# master_devon_routed.net
KiCad netlist of a schematic drawn in EAGLE
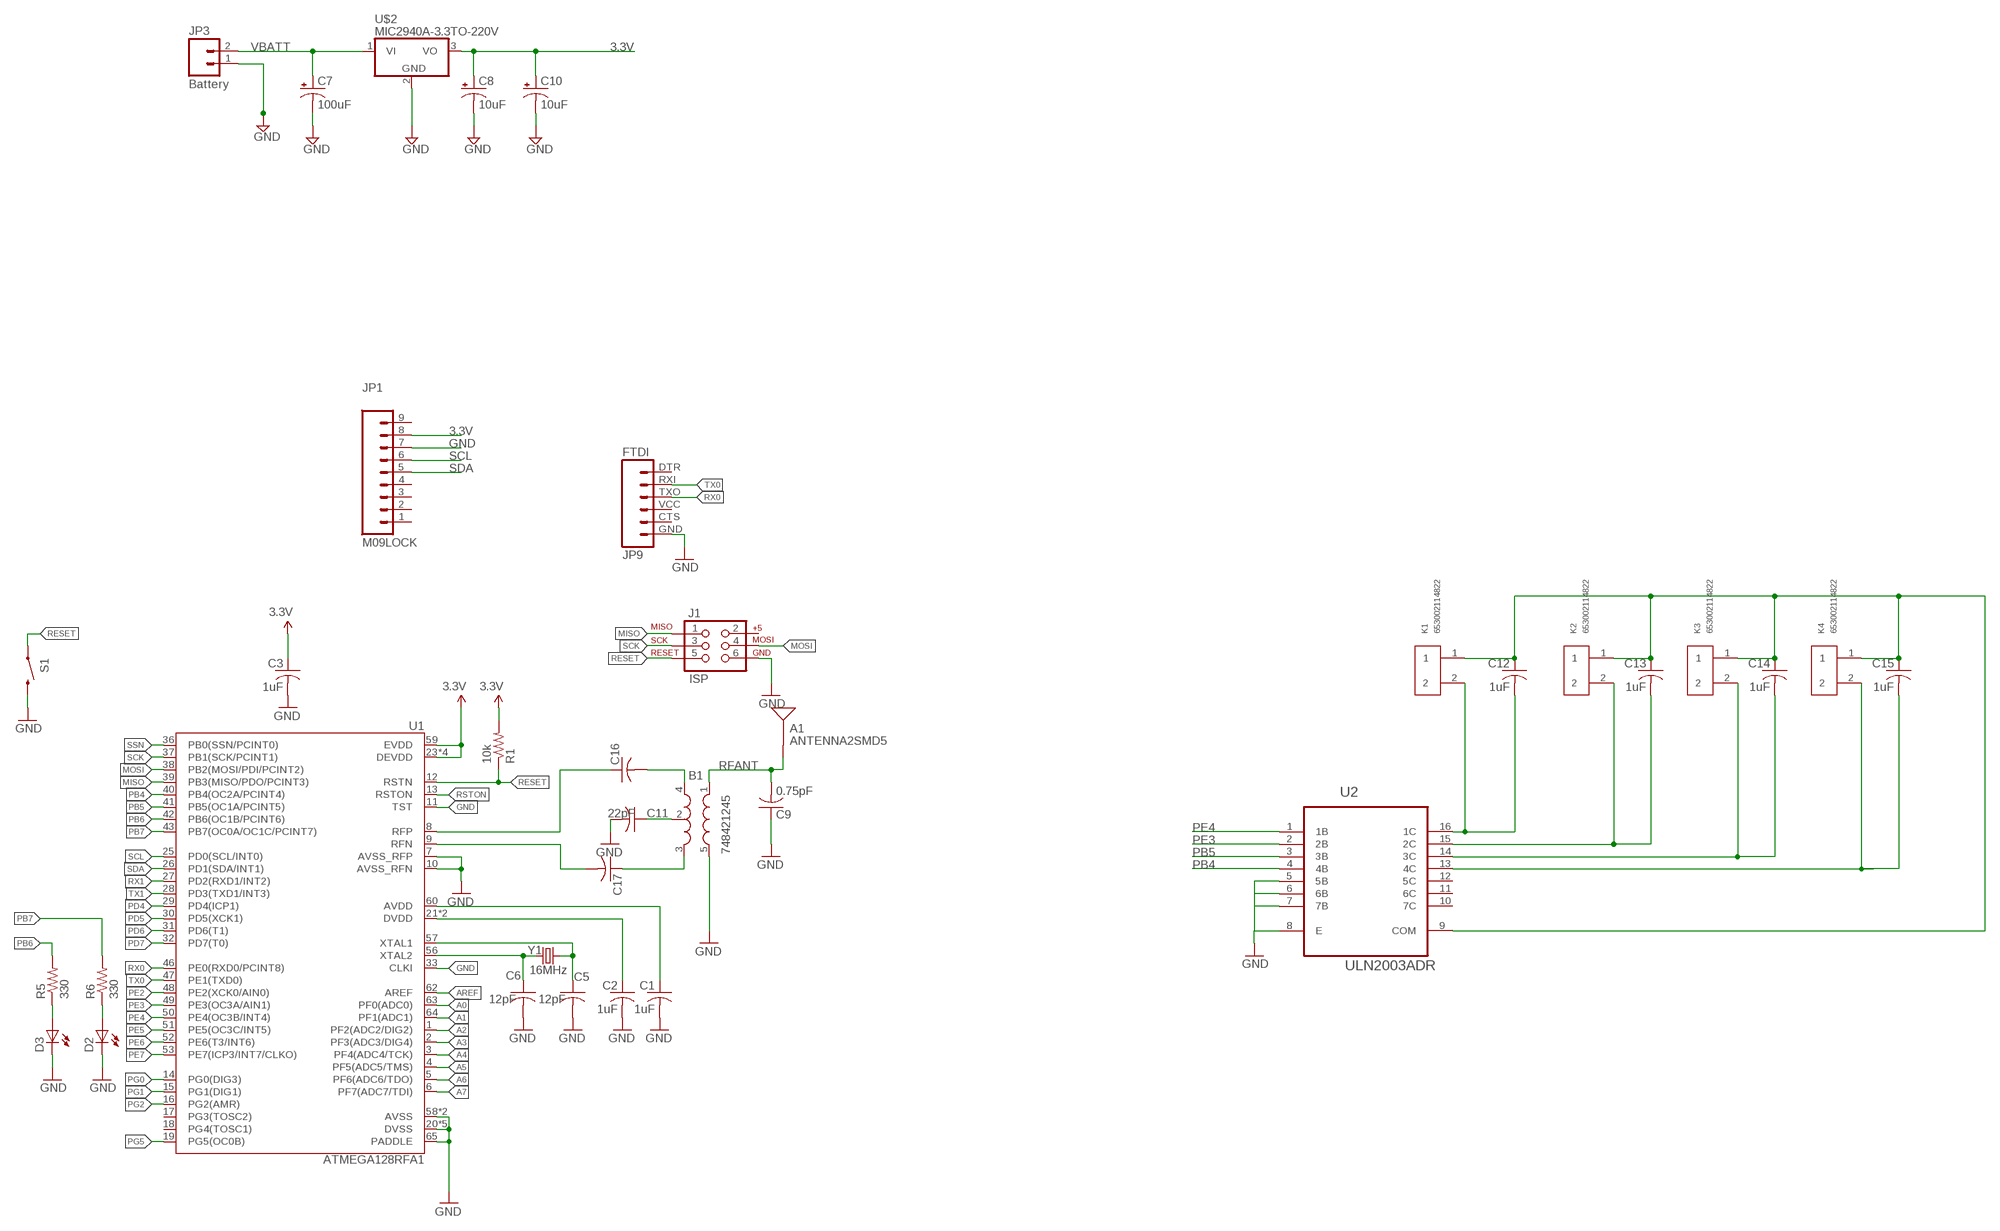
[diagram p0: schematic, sheet 1]

(export (version "E")
  (design (tool "Eeschema 10.0.6"))
  (components
    (comp (ref "A1")
      (value "ANTENNA2SMD5")
      (footprint "eagle-import:ANTENNA-CHIP5")
      (libsource (lib "eagle-import") (part "ANTENNA2SMD5"))
    )
    (comp (ref "B1")
      (value "748421245")
      (footprint "eagle-import:BALUN")
      (libsource (lib "eagle-import") (part "BALUN0805"))
    )
    (comp (ref "C1")
      (value "1uF")
      (footprint "eagle-import:C0805")
      (libsource (lib "eagle-import") (part "C-USC0805"))
    )
    (comp (ref "C2")
      (value "1uF")
      (footprint "eagle-import:C0805")
      (libsource (lib "eagle-import") (part "C-USC0805"))
    )
    (comp (ref "C3")
      (value "1uF")
      (footprint "eagle-import:C0805")
      (libsource (lib "eagle-import") (part "C-USC0805"))
    )
    (comp (ref "C5")
      (value "12pF")
      (footprint "eagle-import:C0805")
      (libsource (lib "eagle-import") (part "C-USC0805"))
    )
    (comp (ref "C6")
      (value "12pF")
      (footprint "eagle-import:C0805")
      (libsource (lib "eagle-import") (part "C-USC0805"))
    )
    (comp (ref "C7")
      (value "100uF")
      (footprint "eagle-import:E3,5-8")
      (libsource (lib "eagle-import") (part "CPOL-USE3.5-8"))
    )
    (comp (ref "C8")
      (value "10uF")
      (footprint "eagle-import:E2,5-5")
      (libsource (lib "eagle-import") (part "CPOL-USE2.5-5"))
    )
    (comp (ref "C9")
      (value "0.75pF")
      (footprint "eagle-import:C0805")
      (libsource (lib "eagle-import") (part "C-USC0805"))
    )
    (comp (ref "C10")
      (value "10uF")
      (footprint "eagle-import:E2,5-5")
      (libsource (lib "eagle-import") (part "CPOL-USE2.5-5"))
    )
    (comp (ref "C11")
      (value "22pF")
      (footprint "eagle-import:C0805")
      (libsource (lib "eagle-import") (part "C-USC0805"))
    )
    (comp (ref "C12")
      (value "1uF")
      (footprint "eagle-import:C0805")
      (libsource (lib "eagle-import") (part "C-USC0805"))
    )
    (comp (ref "C13")
      (value "1uF")
      (footprint "eagle-import:C0805")
      (libsource (lib "eagle-import") (part "C-USC0805"))
    )
    (comp (ref "C14")
      (value "1uF")
      (footprint "eagle-import:C0805")
      (libsource (lib "eagle-import") (part "C-USC0805"))
    )
    (comp (ref "C15")
      (value "1uF")
      (footprint "eagle-import:C0805")
      (libsource (lib "eagle-import") (part "C-USC0805"))
    )
    (comp (ref "C16")
      (value "C-USC0805")
      (footprint "eagle-import:C0805")
      (libsource (lib "eagle-import") (part "C-USC0805"))
    )
    (comp (ref "C17")
      (value "C-USC0805")
      (footprint "eagle-import:C0805")
      (libsource (lib "eagle-import") (part "C-USC0805"))
    )
    (comp (ref "D2")
      (value "LEDCHIP-LED0805")
      (footprint "eagle-import:CHIP-LED0805")
      (libsource (lib "eagle-import") (part "LEDCHIP-LED0805"))
    )
    (comp (ref "D3")
      (value "LEDCHIP-LED0805")
      (footprint "eagle-import:CHIP-LED0805")
      (libsource (lib "eagle-import") (part "LEDCHIP-LED0805"))
    )
    (comp (ref "J1")
      (value "ISP")
      (footprint "eagle-import:2X3-NS")
      (libsource (lib "eagle-import") (part "AVR_SPI_PRG_6NS"))
    )
    (comp (ref "JP1")
      (value "M09LOCK")
      (footprint "eagle-import:1X09_LOCK")
      (libsource (lib "eagle-import") (part "M09LOCK"))
    )
    (comp (ref "JP3")
      (value "Battery")
      (footprint "eagle-import:1X02")
      (libsource (lib "eagle-import") (part "M02PTH"))
    )
    (comp (ref "JP9")
      (value "FTDI")
      (footprint "eagle-import:FTDI_BASIC")
      (libsource (lib "eagle-import") (part "FTDI_BASICPTH"))
    )
    (comp (ref "K1")
      (value "653002114822")
      (footprint "eagle-import:653002114822")
      (libsource (lib "eagle-import") (part "653002114822"))
    )
    (comp (ref "K2")
      (value "653002114822")
      (footprint "eagle-import:653002114822")
      (libsource (lib "eagle-import") (part "653002114822"))
    )
    (comp (ref "K3")
      (value "653002114822")
      (footprint "eagle-import:653002114822")
      (libsource (lib "eagle-import") (part "653002114822"))
    )
    (comp (ref "K4")
      (value "653002114822")
      (footprint "eagle-import:653002114822")
      (libsource (lib "eagle-import") (part "653002114822"))
    )
    (comp (ref "R1")
      (value "10k")
      (footprint "eagle-import:R0805")
      (libsource (lib "eagle-import") (part "R-US_R0805"))
    )
    (comp (ref "R5")
      (value "330")
      (footprint "eagle-import:R0805")
      (libsource (lib "eagle-import") (part "R-US_R0805"))
    )
    (comp (ref "R6")
      (value "330")
      (footprint "eagle-import:R0805")
      (libsource (lib "eagle-import") (part "R-US_R0805"))
    )
    (comp (ref "S1")
      (value "SWITCH-MOMENTARY-2SMD")
      (footprint "eagle-import:TACTILE_SWITCH_SMD")
      (libsource (lib "eagle-import") (part "SWITCH-MOMENTARY-2SMD"))
    )
    (comp (ref "U$2")
      (value "MIC2940A-3.3TO-220V")
      (footprint "eagle-import:TO-220V")
      (libsource (lib "eagle-import") (part "MIC2940A-3.3TO-220V"))
    )
    (comp (ref "U1")
      (value "ATMEGA128RFA1")
      (footprint "eagle-import:QFN-64")
      (libsource (lib "eagle-import") (part "ATMEGA128RFA1"))
    )
    (comp (ref "U2")
      (value "ULN2003ADR")
      (footprint "eagle-import:SOIC127P600X175-16N")
      (libsource (lib "eagle-import") (part "ULN2003ADR"))
    )
    (comp (ref "Y1")
      (value "16MHz")
      (footprint "eagle-import:CRYSTAL-SMD-5X3")
      (libsource (lib "eagle-import") (part "CRYSTAL5X3"))
    )
  )
  (nets
    (net (code "1") (name "/RFANT") (class "Default")
      (node (ref "A1") (pin "FEED") (pinfunction "SIGNAL_FEED") (pintype "bidirectional"))
      (node (ref "B1") (pin "1") (pinfunction "IN_1") (pintype "bidirectional"))
      (node (ref "C9") (pin "2") (pinfunction "2_2") (pintype "passive"))
    )
    (net (code "2") (name "/VBATT") (class "Default")
      (node (ref "C12") (pin "1") (pinfunction "1_1") (pintype "passive"))
      (node (ref "C13") (pin "1") (pinfunction "1_1") (pintype "passive"))
      (node (ref "C14") (pin "1") (pinfunction "1_1") (pintype "passive"))
      (node (ref "C15") (pin "1") (pinfunction "1_1") (pintype "passive"))
      (node (ref "C7") (pin "+") (pinfunction "+_+") (pintype "passive"))
      (node (ref "JP3") (pin "2") (pinfunction "2_2") (pintype "passive"))
      (node (ref "K1") (pin "1") (pinfunction "1_1") (pintype "bidirectional"))
      (node (ref "K2") (pin "1") (pinfunction "1_1") (pintype "bidirectional"))
      (node (ref "K3") (pin "1") (pinfunction "1_1") (pintype "bidirectional"))
      (node (ref "K4") (pin "1") (pinfunction "1_1") (pintype "bidirectional"))
      (node (ref "U$2") (pin "1") (pinfunction "VI_1") (pintype "input"))
      (node (ref "U2") (pin "9") (pinfunction "COM_9") (pintype "output"))
    )
    (net (code "3") (name "3.3V") (class "Default")
      (node (ref "C10") (pin "+") (pinfunction "+_+") (pintype "passive"))
      (node (ref "C3") (pin "1") (pinfunction "1_1") (pintype "passive"))
      (node (ref "C8") (pin "+") (pinfunction "+_+") (pintype "passive"))
      (node (ref "JP1") (pin "8") (pinfunction "8_8") (pintype "passive"))
      (node (ref "R1") (pin "2") (pinfunction "2_2") (pintype "passive"))
      (node (ref "U$2") (pin "3") (pinfunction "VO_3") (pintype "passive"))
      (node (ref "U1") (pin "23") (pinfunction "DEVDD_23") (pintype "bidirectional"))
      (node (ref "U1") (pin "34") (pinfunction "DEVDD_34") (pintype "bidirectional"))
      (node (ref "U1") (pin "44") (pinfunction "DEVDD_44") (pintype "bidirectional"))
      (node (ref "U1") (pin "54") (pinfunction "DEVDD_54") (pintype "bidirectional"))
      (node (ref "U1") (pin "59") (pinfunction "EVDD_59") (pintype "bidirectional"))
    )
    (net (code "4") (name "A0") (class "Default")
      (node (ref "U1") (pin "63") (pinfunction "PF0(ADC0)_63") (pintype "bidirectional"))
    )
    (net (code "5") (name "A1") (class "Default")
      (node (ref "U1") (pin "64") (pinfunction "PF1(ADC1)_64") (pintype "bidirectional"))
    )
    (net (code "6") (name "A2") (class "Default")
      (node (ref "U1") (pin "1") (pinfunction "PF2(ADC2/DIG2)_1") (pintype "bidirectional"))
    )
    (net (code "7") (name "A3") (class "Default")
      (node (ref "U1") (pin "2") (pinfunction "PF3(ADC3/DIG4)_2") (pintype "bidirectional"))
    )
    (net (code "8") (name "A4") (class "Default")
      (node (ref "U1") (pin "3") (pinfunction "PF4(ADC4/TCK)_3") (pintype "bidirectional"))
    )
    (net (code "9") (name "A5") (class "Default")
      (node (ref "U1") (pin "4") (pinfunction "PF5(ADC5/TMS)_4") (pintype "bidirectional"))
    )
    (net (code "10") (name "A6") (class "Default")
      (node (ref "U1") (pin "5") (pinfunction "PF6(ADC6/TDO)_5") (pintype "bidirectional"))
    )
    (net (code "11") (name "A7") (class "Default")
      (node (ref "U1") (pin "6") (pinfunction "PF7(ADC7/TDI)_6") (pintype "bidirectional"))
    )
    (net (code "12") (name "AREF") (class "Default")
      (node (ref "U1") (pin "62") (pinfunction "AREF_62") (pintype "bidirectional"))
    )
    (net (code "13") (name "GND") (class "Default")
      (node (ref "B1") (pin "5") (pinfunction "GND_5") (pintype "bidirectional"))
      (node (ref "C1") (pin "2") (pinfunction "2_2") (pintype "passive"))
      (node (ref "C10") (pin "-") (pinfunction "-_-") (pintype "passive"))
      (node (ref "C11") (pin "2") (pinfunction "2_2") (pintype "passive"))
      (node (ref "C2") (pin "2") (pinfunction "2_2") (pintype "passive"))
      (node (ref "C3") (pin "2") (pinfunction "2_2") (pintype "passive"))
      (node (ref "C5") (pin "2") (pinfunction "2_2") (pintype "passive"))
      (node (ref "C6") (pin "2") (pinfunction "2_2") (pintype "passive"))
      (node (ref "C7") (pin "-") (pinfunction "-_-") (pintype "passive"))
      (node (ref "C8") (pin "-") (pinfunction "-_-") (pintype "passive"))
      (node (ref "C9") (pin "1") (pinfunction "1_1") (pintype "passive"))
      (node (ref "D2") (pin "C") (pinfunction "C_C") (pintype "passive"))
      (node (ref "D3") (pin "C") (pinfunction "C_C") (pintype "passive"))
      (node (ref "J1") (pin "6") (pinfunction "6_6") (pintype "passive"))
      (node (ref "JP1") (pin "7") (pinfunction "7_7") (pintype "passive"))
      (node (ref "JP3") (pin "1") (pinfunction "1_1") (pintype "passive"))
      (node (ref "JP9") (pin "GND") (pinfunction "6_GND") (pintype "passive"))
      (node (ref "S1") (pin "3") (pinfunction "2_3") (pintype "passive"))
      (node (ref "U$2") (pin "2") (pinfunction "GND_2") (pintype "passive"))
      (node (ref "U1") (pin "10") (pinfunction "AVSS_RFN_10") (pintype "bidirectional"))
      (node (ref "U1") (pin "11") (pinfunction "TST_11") (pintype "bidirectional"))
      (node (ref "U1") (pin "20") (pinfunction "DVSS_20") (pintype "bidirectional"))
      (node (ref "U1") (pin "24") (pinfunction "DVSS_24") (pintype "bidirectional"))
      (node (ref "U1") (pin "33") (pinfunction "CLKI_33") (pintype "bidirectional"))
      (node (ref "U1") (pin "35") (pinfunction "DVSS_35") (pintype "bidirectional"))
      (node (ref "U1") (pin "45") (pinfunction "DVSS_45") (pintype "bidirectional"))
      (node (ref "U1") (pin "55") (pinfunction "DVSS_55") (pintype "bidirectional"))
      (node (ref "U1") (pin "58") (pinfunction "AVSS_58") (pintype "bidirectional"))
      (node (ref "U1") (pin "61") (pinfunction "AVSS_61") (pintype "bidirectional"))
      (node (ref "U1") (pin "65") (pinfunction "PADDLE_65") (pintype "bidirectional"))
      (node (ref "U1") (pin "7") (pinfunction "AVSS_RFP_7") (pintype "bidirectional"))
      (node (ref "U2") (pin "5") (pinfunction "5B_5") (pintype "input"))
      (node (ref "U2") (pin "6") (pinfunction "6B_6") (pintype "input"))
      (node (ref "U2") (pin "7") (pinfunction "7B_7") (pintype "input"))
      (node (ref "U2") (pin "8") (pinfunction "E_8") (pintype "input"))
    )
    (net (code "14") (name "MISO") (class "Default")
      (node (ref "J1") (pin "1") (pinfunction "1_1") (pintype "passive"))
      (node (ref "U1") (pin "39") (pinfunction "PB3(MISO/PDO/PCINT3)_39") (pintype "bidirectional"))
    )
    (net (code "15") (name "MOSI") (class "Default")
      (node (ref "J1") (pin "4") (pinfunction "4_4") (pintype "passive"))
      (node (ref "U1") (pin "38") (pinfunction "PB2(MOSI/PDI/PCINT2)_38") (pintype "bidirectional"))
    )
    (net (code "16") (name "Net-(B1-GND-Pad2)") (class "Default")
      (node (ref "B1") (pin "2") (pinfunction "GND_2") (pintype "bidirectional"))
      (node (ref "C11") (pin "1") (pinfunction "1_1") (pintype "passive"))
    )
    (net (code "17") (name "Net-(B1-OUT1)") (class "Default")
      (node (ref "B1") (pin "4") (pinfunction "OUT1_4") (pintype "bidirectional"))
      (node (ref "C16") (pin "2") (pinfunction "2_2") (pintype "passive"))
    )
    (net (code "18") (name "Net-(B1-OUT2)") (class "Default")
      (node (ref "B1") (pin "3") (pinfunction "OUT2_3") (pintype "bidirectional"))
      (node (ref "C17") (pin "1") (pinfunction "1_1") (pintype "passive"))
    )
    (net (code "19") (name "Net-(C2-Pad1)") (class "Default")
      (node (ref "C2") (pin "1") (pinfunction "1_1") (pintype "passive"))
      (node (ref "U1") (pin "21") (pinfunction "DVDD_21") (pintype "bidirectional"))
      (node (ref "U1") (pin "22") (pinfunction "DVDD_22") (pintype "bidirectional"))
    )
    (net (code "20") (name "Net-(D2-PadA)") (class "Default")
      (node (ref "D2") (pin "A") (pinfunction "A_A") (pintype "passive"))
      (node (ref "R6") (pin "1") (pinfunction "1_1") (pintype "passive"))
    )
    (net (code "21") (name "Net-(D3-PadA)") (class "Default")
      (node (ref "D3") (pin "A") (pinfunction "A_A") (pintype "passive"))
      (node (ref "R5") (pin "1") (pinfunction "1_1") (pintype "passive"))
    )
    (net (code "22") (name "Net-(U1-AVDD)") (class "Default")
      (node (ref "C1") (pin "1") (pinfunction "1_1") (pintype "passive"))
      (node (ref "U1") (pin "60") (pinfunction "AVDD_60") (pintype "bidirectional"))
    )
    (net (code "23") (name "Net-(U1-RFN)") (class "Default")
      (node (ref "C17") (pin "2") (pinfunction "2_2") (pintype "passive"))
      (node (ref "U1") (pin "9") (pinfunction "RFN_9") (pintype "bidirectional"))
    )
    (net (code "24") (name "Net-(U1-RFP)") (class "Default")
      (node (ref "C16") (pin "1") (pinfunction "1_1") (pintype "passive"))
      (node (ref "U1") (pin "8") (pinfunction "RFP_8") (pintype "bidirectional"))
    )
    (net (code "25") (name "Net-(U1-XTAL1)") (class "Default")
      (node (ref "C5") (pin "1") (pinfunction "1_1") (pintype "passive"))
      (node (ref "U1") (pin "57") (pinfunction "XTAL1_57") (pintype "bidirectional"))
      (node (ref "Y1") (pin "3") (pinfunction "2_3") (pintype "passive"))
    )
    (net (code "26") (name "Net-(U1-XTAL2)") (class "Default")
      (node (ref "C6") (pin "1") (pinfunction "1_1") (pintype "passive"))
      (node (ref "U1") (pin "56") (pinfunction "XTAL2_56") (pintype "bidirectional"))
      (node (ref "Y1") (pin "1") (pinfunction "1_1") (pintype "passive"))
    )
    (net (code "27") (name "Net-(U2-1C)") (class "Default")
      (node (ref "C12") (pin "2") (pinfunction "2_2") (pintype "passive"))
      (node (ref "K1") (pin "2") (pinfunction "2_2") (pintype "bidirectional"))
      (node (ref "U2") (pin "16") (pinfunction "1C_16") (pintype "output"))
    )
    (net (code "28") (name "Net-(U2-2C)") (class "Default")
      (node (ref "C13") (pin "2") (pinfunction "2_2") (pintype "passive"))
      (node (ref "K2") (pin "2") (pinfunction "2_2") (pintype "bidirectional"))
      (node (ref "U2") (pin "15") (pinfunction "2C_15") (pintype "output"))
    )
    (net (code "29") (name "Net-(U2-3C)") (class "Default")
      (node (ref "C14") (pin "2") (pinfunction "2_2") (pintype "passive"))
      (node (ref "K3") (pin "2") (pinfunction "2_2") (pintype "bidirectional"))
      (node (ref "U2") (pin "14") (pinfunction "3C_14") (pintype "output"))
    )
    (net (code "30") (name "Net-(U2-4C)") (class "Default")
      (node (ref "C15") (pin "2") (pinfunction "2_2") (pintype "passive"))
      (node (ref "K4") (pin "2") (pinfunction "2_2") (pintype "bidirectional"))
      (node (ref "U2") (pin "13") (pinfunction "4C_13") (pintype "output"))
    )
    (net (code "31") (name "PB4") (class "Default")
      (node (ref "U1") (pin "40") (pinfunction "PB4(OC2A/PCINT4)_40") (pintype "bidirectional"))
      (node (ref "U2") (pin "4") (pinfunction "4B_4") (pintype "input"))
    )
    (net (code "32") (name "PB5") (class "Default")
      (node (ref "U1") (pin "41") (pinfunction "PB5(OC1A/PCINT5)_41") (pintype "bidirectional"))
      (node (ref "U2") (pin "3") (pinfunction "3B_3") (pintype "input"))
    )
    (net (code "33") (name "PB6") (class "Default")
      (node (ref "R5") (pin "2") (pinfunction "2_2") (pintype "passive"))
      (node (ref "U1") (pin "42") (pinfunction "PB6(OC1B/PCINT6)_42") (pintype "bidirectional"))
    )
    (net (code "34") (name "PB7") (class "Default")
      (node (ref "R6") (pin "2") (pinfunction "2_2") (pintype "passive"))
      (node (ref "U1") (pin "43") (pinfunction "PB7(OC0A/OC1C/PCINT7)_43") (pintype "bidirectional"))
    )
    (net (code "35") (name "PD4") (class "Default")
      (node (ref "U1") (pin "29") (pinfunction "PD4(ICP1)_29") (pintype "bidirectional"))
    )
    (net (code "36") (name "PD5") (class "Default")
      (node (ref "U1") (pin "30") (pinfunction "PD5(XCK1)_30") (pintype "bidirectional"))
    )
    (net (code "37") (name "PD6") (class "Default")
      (node (ref "U1") (pin "31") (pinfunction "PD6(T1)_31") (pintype "bidirectional"))
    )
    (net (code "38") (name "PD7") (class "Default")
      (node (ref "U1") (pin "32") (pinfunction "PD7(T0)_32") (pintype "bidirectional"))
    )
    (net (code "39") (name "PE2") (class "Default")
      (node (ref "U1") (pin "48") (pinfunction "PE2(XCK0/AIN0)_48") (pintype "bidirectional"))
    )
    (net (code "40") (name "PE3") (class "Default")
      (node (ref "U1") (pin "49") (pinfunction "PE3(OC3A/AIN1)_49") (pintype "bidirectional"))
      (node (ref "U2") (pin "2") (pinfunction "2B_2") (pintype "input"))
    )
    (net (code "41") (name "PE4") (class "Default")
      (node (ref "U1") (pin "50") (pinfunction "PE4(OC3B/INT4)_50") (pintype "bidirectional"))
      (node (ref "U2") (pin "1") (pinfunction "1B_1") (pintype "input"))
    )
    (net (code "42") (name "PE5") (class "Default")
      (node (ref "U1") (pin "51") (pinfunction "PE5(OC3C/INT5)_51") (pintype "bidirectional"))
    )
    (net (code "43") (name "PE6") (class "Default")
      (node (ref "U1") (pin "52") (pinfunction "PE6(T3/INT6)_52") (pintype "bidirectional"))
    )
    (net (code "44") (name "PE7") (class "Default")
      (node (ref "U1") (pin "53") (pinfunction "PE7(ICP3/INT7/CLKO)_53") (pintype "bidirectional"))
    )
    (net (code "45") (name "PG0") (class "Default")
      (node (ref "U1") (pin "14") (pinfunction "PG0(DIG3)_14") (pintype "bidirectional"))
    )
    (net (code "46") (name "PG1") (class "Default")
      (node (ref "U1") (pin "15") (pinfunction "PG1(DIG1)_15") (pintype "bidirectional"))
    )
    (net (code "47") (name "PG2") (class "Default")
      (node (ref "U1") (pin "16") (pinfunction "PG2(AMR)_16") (pintype "bidirectional"))
    )
    (net (code "48") (name "PG5") (class "Default")
      (node (ref "U1") (pin "19") (pinfunction "PG5(OC0B)_19") (pintype "bidirectional"))
    )
    (net (code "49") (name "RESET") (class "Default")
      (node (ref "J1") (pin "5") (pinfunction "5_5") (pintype "passive"))
      (node (ref "R1") (pin "1") (pinfunction "1_1") (pintype "passive"))
      (node (ref "S1") (pin "1") (pinfunction "1_1") (pintype "passive"))
      (node (ref "U1") (pin "12") (pinfunction "RSTN_12") (pintype "bidirectional"))
    )
    (net (code "50") (name "RSTON") (class "Default")
      (node (ref "U1") (pin "13") (pinfunction "RSTON_13") (pintype "bidirectional"))
    )
    (net (code "51") (name "RX0") (class "Default")
      (node (ref "JP9") (pin "TXO") (pinfunction "3_TXO") (pintype "passive"))
      (node (ref "U1") (pin "46") (pinfunction "PE0(RXD0/PCINT8)_46") (pintype "bidirectional"))
    )
    (net (code "52") (name "RX1") (class "Default")
      (node (ref "U1") (pin "27") (pinfunction "PD2(RXD1/INT2)_27") (pintype "bidirectional"))
    )
    (net (code "53") (name "SCK") (class "Default")
      (node (ref "J1") (pin "3") (pinfunction "3_3") (pintype "passive"))
      (node (ref "U1") (pin "37") (pinfunction "PB1(SCK/PCINT1)_37") (pintype "bidirectional"))
    )
    (net (code "54") (name "SCL") (class "Default")
      (node (ref "JP1") (pin "6") (pinfunction "6_6") (pintype "passive"))
      (node (ref "U1") (pin "25") (pinfunction "PD0(SCL/INT0)_25") (pintype "bidirectional"))
    )
    (net (code "55") (name "SDA") (class "Default")
      (node (ref "JP1") (pin "5") (pinfunction "5_5") (pintype "passive"))
      (node (ref "U1") (pin "26") (pinfunction "PD1(SDA/INT1)_26") (pintype "bidirectional"))
    )
    (net (code "56") (name "SSN") (class "Default")
      (node (ref "U1") (pin "36") (pinfunction "PB0(SSN/PCINT0)_36") (pintype "bidirectional"))
    )
    (net (code "57") (name "TX0") (class "Default")
      (node (ref "JP9") (pin "RXI") (pinfunction "2_RXI") (pintype "passive"))
      (node (ref "U1") (pin "47") (pinfunction "PE1(TXD0)_47") (pintype "bidirectional"))
    )
    (net (code "58") (name "TX1") (class "Default")
      (node (ref "U1") (pin "28") (pinfunction "PD3(TXD1/INT3)_28") (pintype "bidirectional"))
    )
    (net (code "59") (name "unconnected-(J1-Pad2)") (class "Default")
      (node (ref "J1") (pin "2") (pinfunction "2_2") (pintype "passive"))
    )
    (net (code "60") (name "unconnected-(JP1-Pad1)") (class "Default")
      (node (ref "JP1") (pin "1") (pinfunction "1_1") (pintype "passive"))
    )
    (net (code "61") (name "unconnected-(JP1-Pad2)") (class "Default")
      (node (ref "JP1") (pin "2") (pinfunction "2_2") (pintype "passive"))
    )
    (net (code "62") (name "unconnected-(JP1-Pad3)") (class "Default")
      (node (ref "JP1") (pin "3") (pinfunction "3_3") (pintype "passive"))
    )
    (net (code "63") (name "unconnected-(JP1-Pad4)") (class "Default")
      (node (ref "JP1") (pin "4") (pinfunction "4_4") (pintype "passive"))
    )
    (net (code "64") (name "unconnected-(JP1-Pad9)") (class "Default")
      (node (ref "JP1") (pin "9") (pinfunction "9_9") (pintype "passive"))
    )
    (net (code "65") (name "unconnected-(JP9-1-PadDTR)") (class "Default")
      (node (ref "JP9") (pin "DTR") (pinfunction "1_DTR") (pintype "passive"))
    )
    (net (code "66") (name "unconnected-(JP9-4-PadVCC)") (class "Default")
      (node (ref "JP9") (pin "VCC") (pinfunction "4_VCC") (pintype "passive"))
    )
    (net (code "67") (name "unconnected-(JP9-5-PadCTS)") (class "Default")
      (node (ref "JP9") (pin "CTS") (pinfunction "5_CTS") (pintype "passive"))
    )
    (net (code "68") (name "unconnected-(U1-PG3(TOSC2)-Pad17)") (class "Default")
      (node (ref "U1") (pin "17") (pinfunction "PG3(TOSC2)_17") (pintype "bidirectional"))
    )
    (net (code "69") (name "unconnected-(U1-PG4(TOSC1)-Pad18)") (class "Default")
      (node (ref "U1") (pin "18") (pinfunction "PG4(TOSC1)_18") (pintype "bidirectional"))
    )
    (net (code "70") (name "unconnected-(U2-5C-Pad12)") (class "Default")
      (node (ref "U2") (pin "12") (pinfunction "5C_12") (pintype "output"))
    )
    (net (code "71") (name "unconnected-(U2-6C-Pad11)") (class "Default")
      (node (ref "U2") (pin "11") (pinfunction "6C_11") (pintype "output"))
    )
    (net (code "72") (name "unconnected-(U2-7C-Pad10)") (class "Default")
      (node (ref "U2") (pin "10") (pinfunction "7C_10") (pintype "output"))
    )
  )
)
